# QFP32_DIP.net
KiCad netlist of a schematic drawn in EAGLE
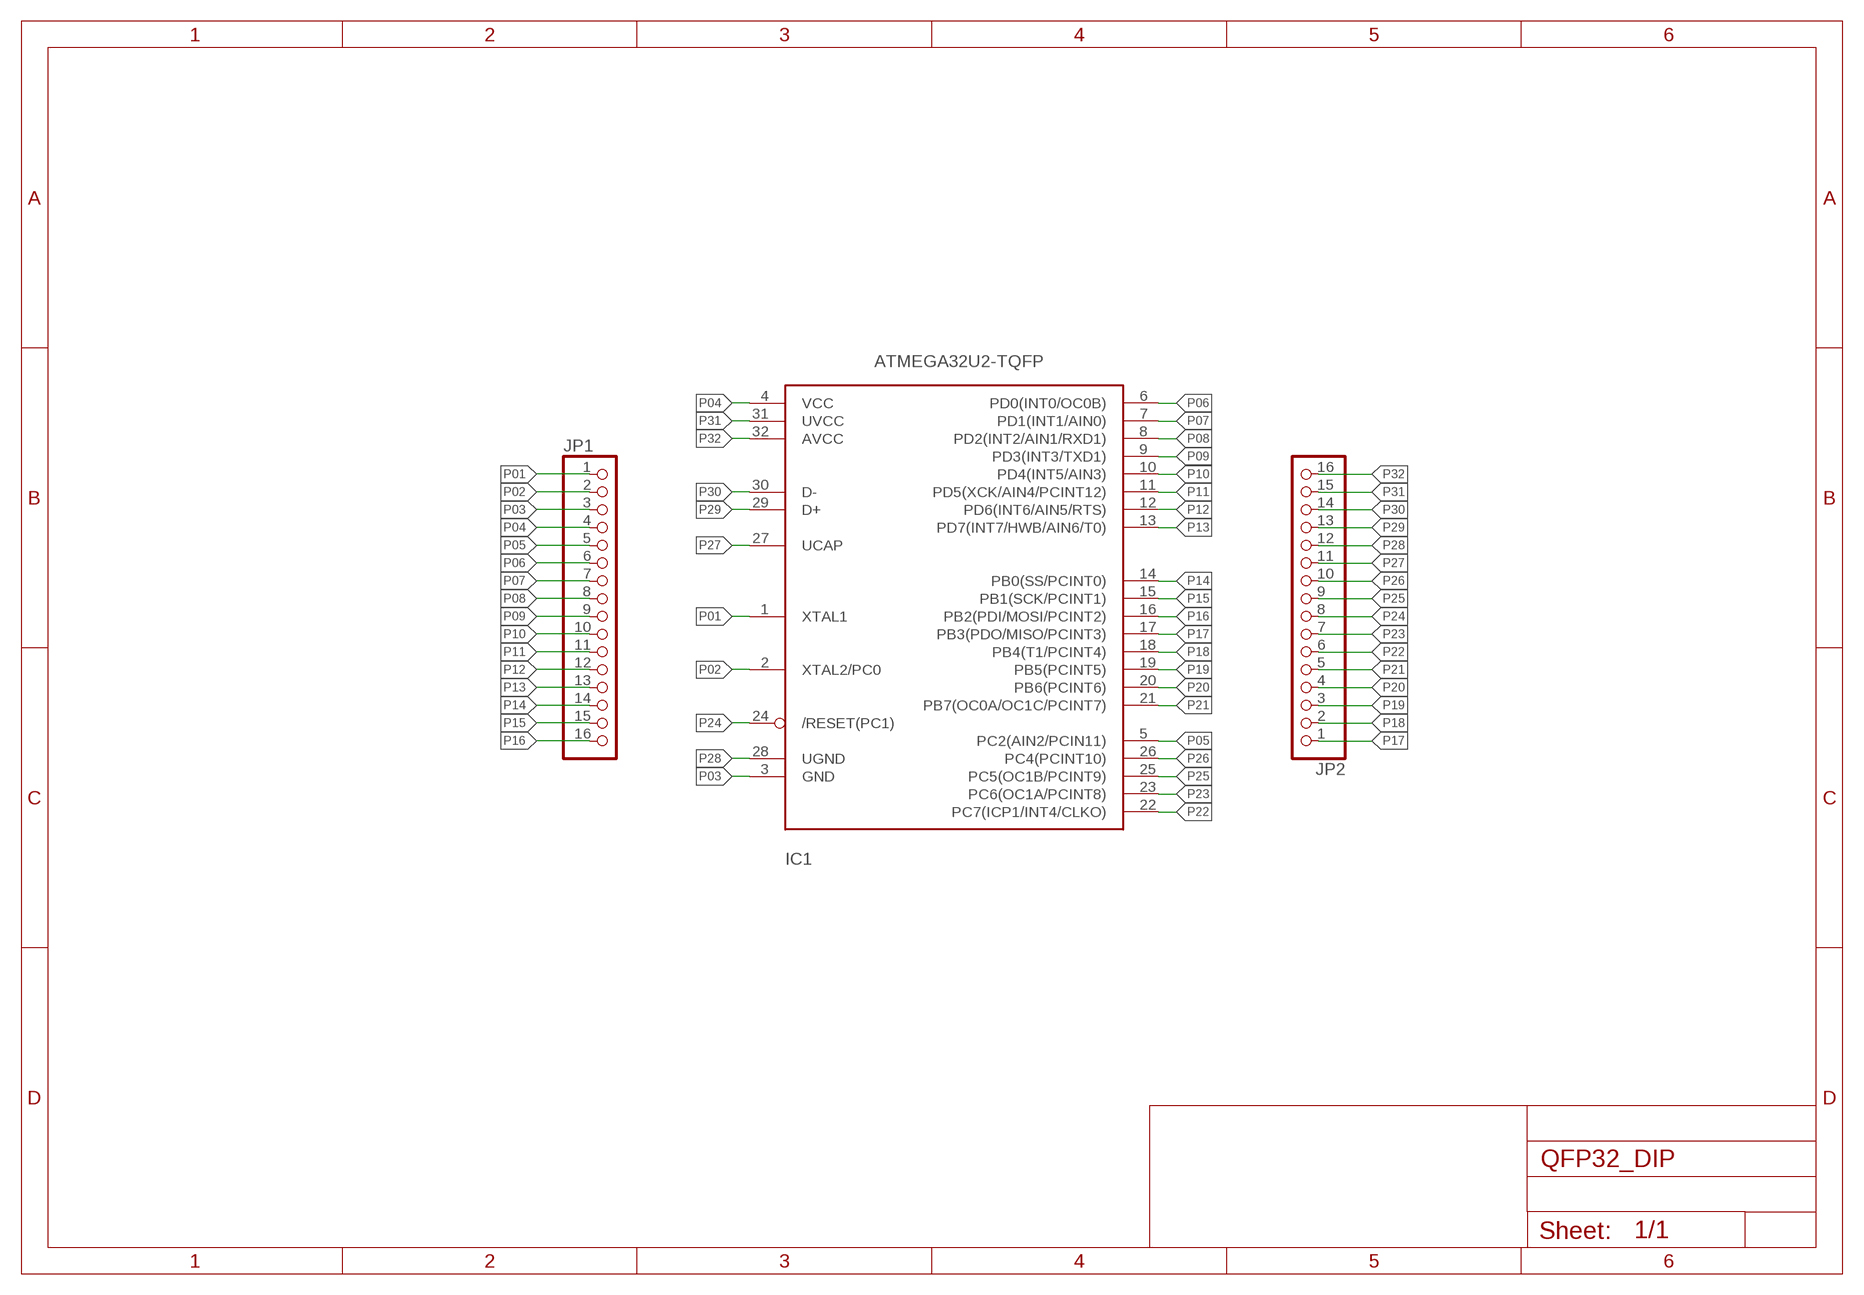
[diagram p0: schematic, sheet 1]

(export (version "E")
  (design (tool "Eeschema 10.0.6"))
  (components
    (comp (ref "IC1")
      (value "ATMEGA32U2-TQFP")
      (footprint "eagle-import:TQFP32-08")
      (libsource (lib "eagle-import") (part "ATMEGA32U2-TQFP"))
    )
    (comp (ref "JP1")
      (value "PINHD-1X16")
      (footprint "eagle-import:1X16")
      (libsource (lib "eagle-import") (part "PINHD-1X16"))
    )
    (comp (ref "JP2")
      (value "PINHD-1X16")
      (footprint "eagle-import:1X16")
      (libsource (lib "eagle-import") (part "PINHD-1X16"))
    )
  )
  (nets
    (net (code "1") (name "P01") (class "Default")
      (node (ref "IC1") (pin "1") (pinfunction "XTAL1_1") (pintype "bidirectional"))
      (node (ref "JP1") (pin "1") (pinfunction "1_1") (pintype "passive"))
    )
    (net (code "2") (name "P02") (class "Default")
      (node (ref "IC1") (pin "2") (pinfunction "XTAL2/PC0_2") (pintype "bidirectional"))
      (node (ref "JP1") (pin "2") (pinfunction "2_2") (pintype "passive"))
    )
    (net (code "3") (name "P03") (class "Default")
      (node (ref "IC1") (pin "3") (pinfunction "GND_3") (pintype "bidirectional"))
      (node (ref "JP1") (pin "3") (pinfunction "3_3") (pintype "passive"))
    )
    (net (code "4") (name "P04") (class "Default")
      (node (ref "IC1") (pin "4") (pinfunction "VCC_4") (pintype "bidirectional"))
      (node (ref "JP1") (pin "4") (pinfunction "4_4") (pintype "passive"))
    )
    (net (code "5") (name "P05") (class "Default")
      (node (ref "IC1") (pin "5") (pinfunction "PC2(AIN2/PCIN11)_5") (pintype "bidirectional"))
      (node (ref "JP1") (pin "5") (pinfunction "5_5") (pintype "passive"))
    )
    (net (code "6") (name "P06") (class "Default")
      (node (ref "IC1") (pin "6") (pinfunction "PD0(INT0/OC0B)_6") (pintype "bidirectional"))
      (node (ref "JP1") (pin "6") (pinfunction "6_6") (pintype "passive"))
    )
    (net (code "7") (name "P07") (class "Default")
      (node (ref "IC1") (pin "7") (pinfunction "PD1(INT1/AIN0)_7") (pintype "bidirectional"))
      (node (ref "JP1") (pin "7") (pinfunction "7_7") (pintype "passive"))
    )
    (net (code "8") (name "P08") (class "Default")
      (node (ref "IC1") (pin "8") (pinfunction "PD2(INT2/AIN1/RXD1)_8") (pintype "bidirectional"))
      (node (ref "JP1") (pin "8") (pinfunction "8_8") (pintype "passive"))
    )
    (net (code "9") (name "P09") (class "Default")
      (node (ref "IC1") (pin "9") (pinfunction "PD3(INT3/TXD1)_9") (pintype "bidirectional"))
      (node (ref "JP1") (pin "9") (pinfunction "9_9") (pintype "passive"))
    )
    (net (code "10") (name "P10") (class "Default")
      (node (ref "IC1") (pin "10") (pinfunction "PD4(INT5/AIN3)_10") (pintype "bidirectional"))
      (node (ref "JP1") (pin "10") (pinfunction "10_10") (pintype "passive"))
    )
    (net (code "11") (name "P11") (class "Default")
      (node (ref "IC1") (pin "11") (pinfunction "PD5(XCK/AIN4/PCINT12)_11") (pintype "bidirectional"))
      (node (ref "JP1") (pin "11") (pinfunction "11_11") (pintype "passive"))
    )
    (net (code "12") (name "P12") (class "Default")
      (node (ref "IC1") (pin "12") (pinfunction "PD6(INT6/AIN5/RTS)_12") (pintype "bidirectional"))
      (node (ref "JP1") (pin "12") (pinfunction "12_12") (pintype "passive"))
    )
    (net (code "13") (name "P13") (class "Default")
      (node (ref "IC1") (pin "13") (pinfunction "PD7(INT7/HWB/AIN6/T0)_13") (pintype "bidirectional"))
      (node (ref "JP1") (pin "13") (pinfunction "13_13") (pintype "passive"))
    )
    (net (code "14") (name "P14") (class "Default")
      (node (ref "IC1") (pin "14") (pinfunction "PB0(SS/PCINT0)_14") (pintype "bidirectional"))
      (node (ref "JP1") (pin "14") (pinfunction "14_14") (pintype "passive"))
    )
    (net (code "15") (name "P15") (class "Default")
      (node (ref "IC1") (pin "15") (pinfunction "PB1(SCK/PCINT1)_15") (pintype "bidirectional"))
      (node (ref "JP1") (pin "15") (pinfunction "15_15") (pintype "passive"))
    )
    (net (code "16") (name "P16") (class "Default")
      (node (ref "IC1") (pin "16") (pinfunction "PB2(PDI/MOSI/PCINT2)_16") (pintype "bidirectional"))
      (node (ref "JP1") (pin "16") (pinfunction "16_16") (pintype "passive"))
    )
    (net (code "17") (name "P17") (class "Default")
      (node (ref "IC1") (pin "17") (pinfunction "PB3(PDO/MISO/PCINT3)_17") (pintype "bidirectional"))
      (node (ref "JP2") (pin "1") (pinfunction "1_1") (pintype "passive"))
    )
    (net (code "18") (name "P18") (class "Default")
      (node (ref "IC1") (pin "18") (pinfunction "PB4(T1/PCINT4)_18") (pintype "bidirectional"))
      (node (ref "JP2") (pin "2") (pinfunction "2_2") (pintype "passive"))
    )
    (net (code "19") (name "P19") (class "Default")
      (node (ref "IC1") (pin "19") (pinfunction "PB5(PCINT5)_19") (pintype "bidirectional"))
      (node (ref "JP2") (pin "3") (pinfunction "3_3") (pintype "passive"))
    )
    (net (code "20") (name "P20") (class "Default")
      (node (ref "IC1") (pin "20") (pinfunction "PB6(PCINT6)_20") (pintype "bidirectional"))
      (node (ref "JP2") (pin "4") (pinfunction "4_4") (pintype "passive"))
    )
    (net (code "21") (name "P21") (class "Default")
      (node (ref "IC1") (pin "21") (pinfunction "PB7(OC0A/OC1C/PCINT7)_21") (pintype "bidirectional"))
      (node (ref "JP2") (pin "5") (pinfunction "5_5") (pintype "passive"))
    )
    (net (code "22") (name "P22") (class "Default")
      (node (ref "IC1") (pin "22") (pinfunction "PC7(ICP1/INT4/CLKO)_22") (pintype "bidirectional"))
      (node (ref "JP2") (pin "6") (pinfunction "6_6") (pintype "passive"))
    )
    (net (code "23") (name "P23") (class "Default")
      (node (ref "IC1") (pin "23") (pinfunction "PC6(OC1A/PCINT8)_23") (pintype "bidirectional"))
      (node (ref "JP2") (pin "7") (pinfunction "7_7") (pintype "passive"))
    )
    (net (code "24") (name "P24") (class "Default")
      (node (ref "IC1") (pin "24") (pinfunction "/RESET(PC1)_24") (pintype "bidirectional"))
      (node (ref "JP2") (pin "8") (pinfunction "8_8") (pintype "passive"))
    )
    (net (code "25") (name "P25") (class "Default")
      (node (ref "IC1") (pin "25") (pinfunction "PC5(OC1B/PCINT9)_25") (pintype "bidirectional"))
      (node (ref "JP2") (pin "9") (pinfunction "9_9") (pintype "passive"))
    )
    (net (code "26") (name "P26") (class "Default")
      (node (ref "IC1") (pin "26") (pinfunction "PC4(PCINT10)_26") (pintype "bidirectional"))
      (node (ref "JP2") (pin "10") (pinfunction "10_10") (pintype "passive"))
    )
    (net (code "27") (name "P27") (class "Default")
      (node (ref "IC1") (pin "27") (pinfunction "UCAP_27") (pintype "bidirectional"))
      (node (ref "JP2") (pin "11") (pinfunction "11_11") (pintype "passive"))
    )
    (net (code "28") (name "P28") (class "Default")
      (node (ref "IC1") (pin "28") (pinfunction "UGND_28") (pintype "bidirectional"))
      (node (ref "JP2") (pin "12") (pinfunction "12_12") (pintype "passive"))
    )
    (net (code "29") (name "P29") (class "Default")
      (node (ref "IC1") (pin "29") (pinfunction "D+_29") (pintype "bidirectional"))
      (node (ref "JP2") (pin "13") (pinfunction "13_13") (pintype "passive"))
    )
    (net (code "30") (name "P30") (class "Default")
      (node (ref "IC1") (pin "30") (pinfunction "D-_30") (pintype "bidirectional"))
      (node (ref "JP2") (pin "14") (pinfunction "14_14") (pintype "passive"))
    )
    (net (code "31") (name "P31") (class "Default")
      (node (ref "IC1") (pin "31") (pinfunction "UVCC_31") (pintype "bidirectional"))
      (node (ref "JP2") (pin "15") (pinfunction "15_15") (pintype "passive"))
    )
    (net (code "32") (name "P32") (class "Default")
      (node (ref "IC1") (pin "32") (pinfunction "AVCC_32") (pintype "bidirectional"))
      (node (ref "JP2") (pin "16") (pinfunction "16_16") (pintype "passive"))
    )
  )
)
